# Kvant3DPrinter.net
KiCad netlist of a schematic drawn in Altium Designer
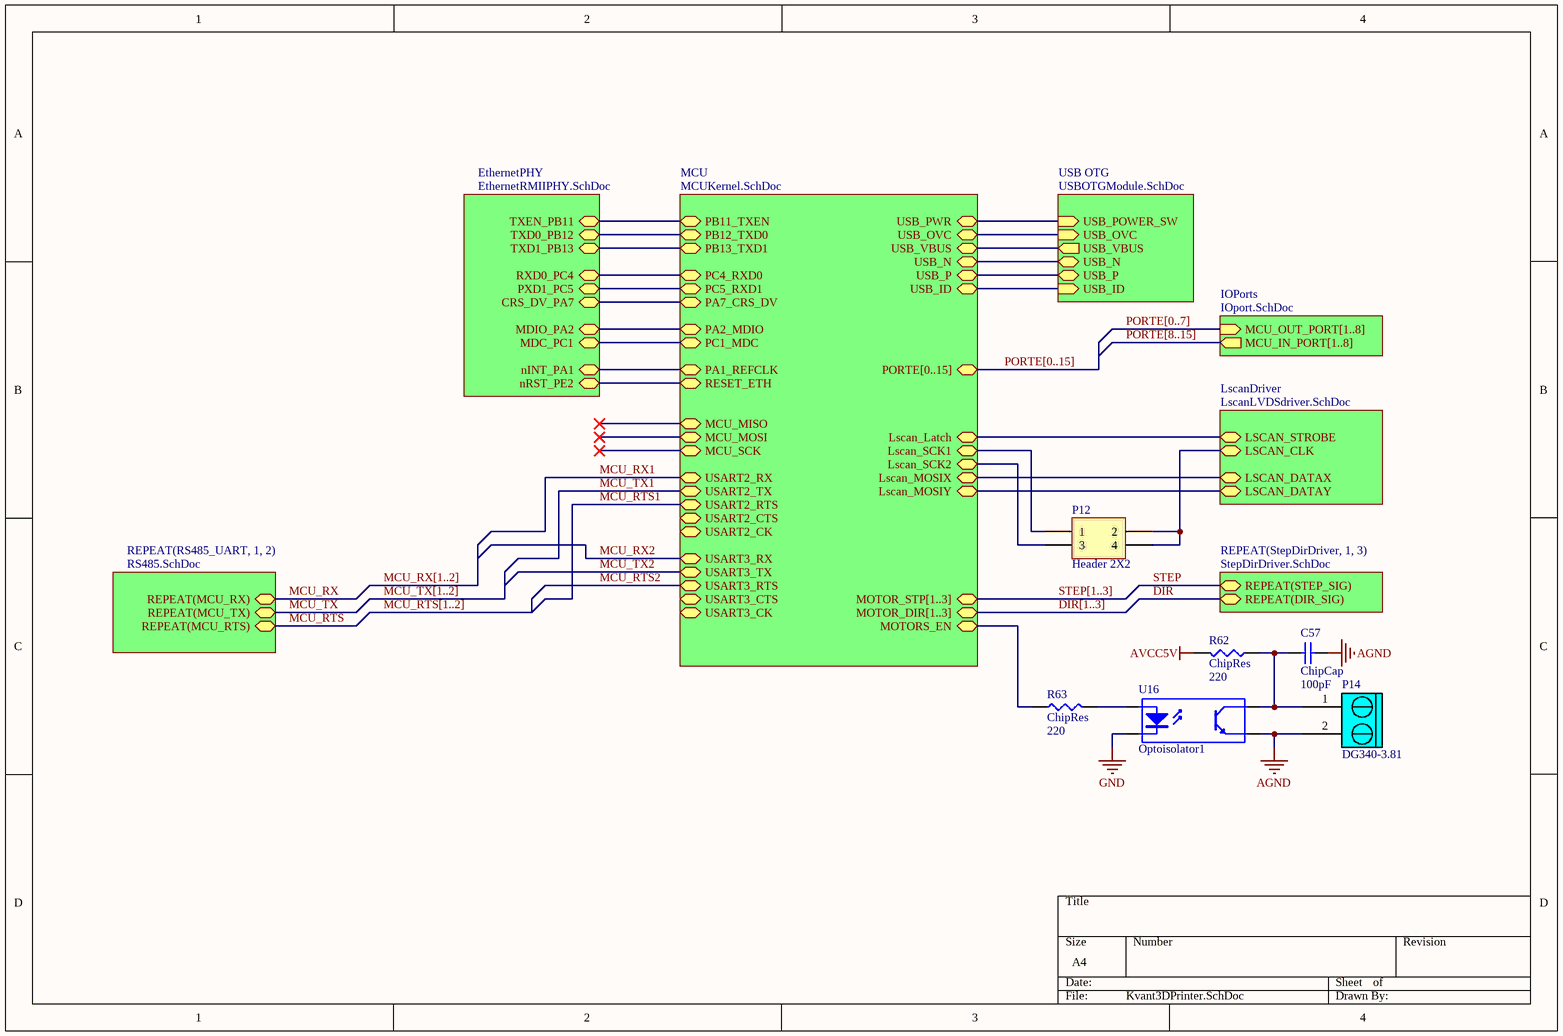
[diagram p0: Kvant3DPrinter.SchDoc]

(export (version "E")
  (design (tool "Eeschema 10.0.6"))
  (components
    (comp (ref "C57")
      (value "ChipCap")
      (footprint "CAP0805")
      (description "Capacitor")
      (fields (field (name "ALTIUM_VALUE") "100pF") (field (name "PUBLISHER") "Altium Limited"))
      (libsource (lib "Common Devices") (part "ChipCap"))
    )
    (comp (ref "P12")
      (value "Header 2X2")
      (footprint "HDR2X2")
      (description "Header, 2-Pin, Dual row")
      (fields (field (name "PUBLISHER") "Altium Limited"))
      (libsource (lib "Miscellaneous Connectors") (part "Header 2X2"))
    )
    (comp (ref "P14")
      (value "DG340-3.81")
      (footprint "DG340-3.81-02P-00A(H)")
      (description "Terminal block")
      (libsource (lib "Connectors") (part "DG340-3.81-02P"))
    )
    (comp (ref "R62")
      (value "ChipRes")
      (footprint "RES0805")
      (description "Chip resistor")
      (fields (field (name "ALTIUM_VALUE") "220"))
      (libsource (lib "Common Devices") (part "ChipRes"))
    )
    (comp (ref "R63")
      (value "ChipRes")
      (footprint "RES0805")
      (description "Chip resistor")
      (fields (field (name "ALTIUM_VALUE") "220"))
      (libsource (lib "Common Devices") (part "ChipRes"))
    )
    (comp (ref "U16")
      (value "Optoisolator1")
      (footprint "DIP-4")
      (description "4-Pin Phototransistor Optocoupler")
      (fields (field (name "PUBLISHER") "Altium Limited"))
      (libsource (lib "Miscellaneous Devices") (part "Optoisolator1"))
    )
  )
  (nets
    (net (code "26") (name "/LSCAN_CLK") (class "Default")
      (node (ref "P12") (pin "2") (pinfunction "2_2") (pintype "passive"))
      (node (ref "P12") (pin "4") (pinfunction "4_4") (pintype "passive"))
    )
    (net (code "30") (name "/Lscan_SCK1") (class "Default")
      (node (ref "P12") (pin "1") (pinfunction "1_1") (pintype "passive"))
    )
    (net (code "31") (name "/Lscan_SCK2") (class "Default")
      (node (ref "P12") (pin "3") (pinfunction "3_3") (pintype "passive"))
    )
    (net (code "49") (name "/MOTORS_EN") (class "Default") (node (ref "R63") (pin "1") (pintype "passive")))
    (net (code "72") (name "AGND") (class "Default")
      (node (ref "C57") (pin "2") (pinfunction "2_2") (pintype "passive"))
      (node (ref "P14") (pin "2") (pinfunction "2_2") (pintype "passive"))
      (node (ref "U16") (pin "3") (pinfunction "E_3") (pintype "passive"))
    )
    (net (code "73") (name "AVCC5V") (class "Default") (node (ref "R62") (pin "2") (pintype "passive")))
    (net (code "74") (name "GND") (class "Default")
      (node (ref "U16") (pin "2") (pinfunction "K_2") (pintype "passive"))
    )
    (net (code "75") (name "Net-(U16-A)") (class "Default")
      (node (ref "R63") (pin "2") (pintype "passive"))
      (node (ref "U16") (pin "1") (pinfunction "A_1") (pintype "passive"))
    )
    (net (code "76") (name "Net-(U16-C)") (class "Default")
      (node (ref "C57") (pin "1") (pinfunction "1_1") (pintype "passive"))
      (node (ref "P14") (pin "1") (pinfunction "1_1") (pintype "passive"))
      (node (ref "R62") (pin "1") (pintype "passive"))
      (node (ref "U16") (pin "4") (pinfunction "C_4") (pintype "passive"))
    )
  )
)
